# LTF1.net
KiCad netlist of a schematic drawn in EAGLE
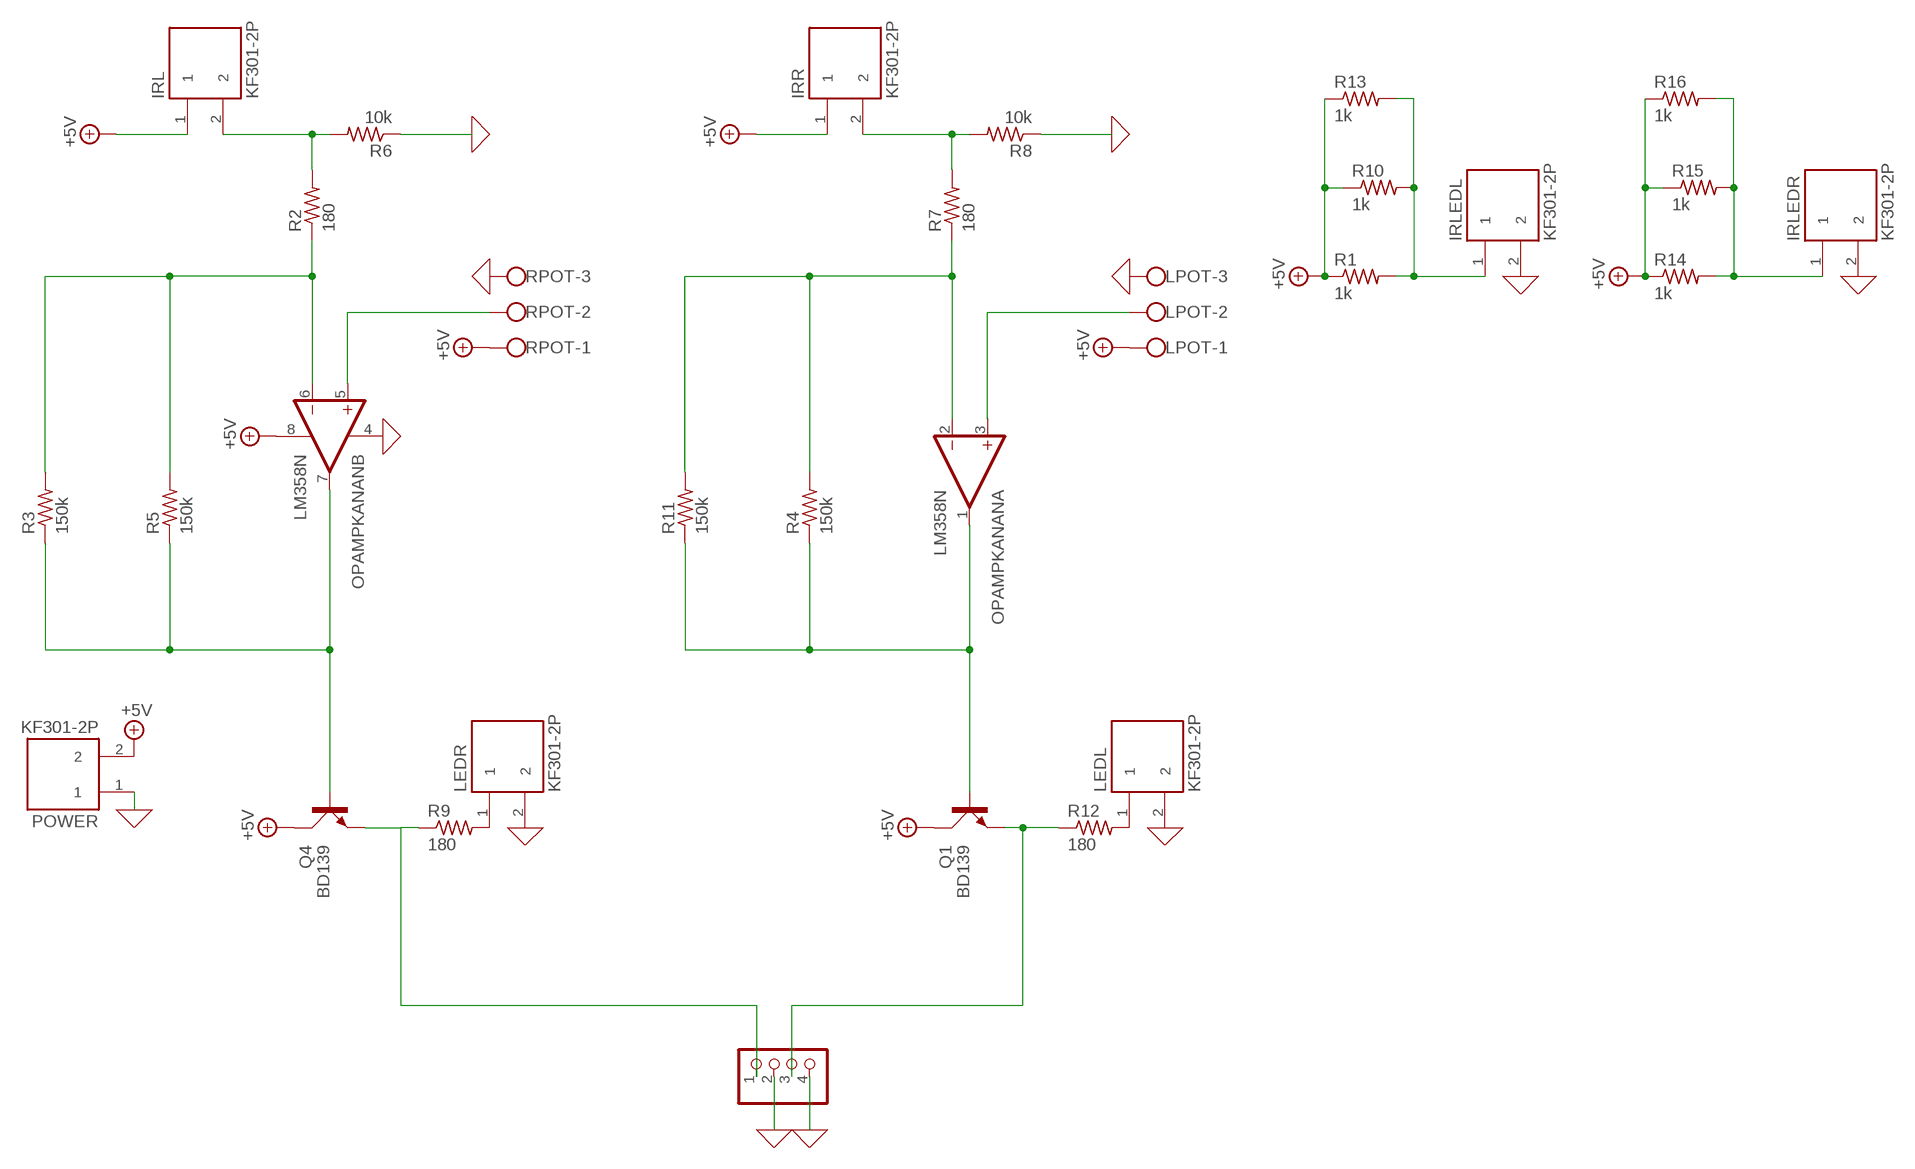
[diagram p0: schematic, sheet 1]

(export (version "E")
  (design (tool "Eeschema 10.0.6"))
  (components
    (comp (ref "IRL")
      (value "KF301-2P")
      (footprint "eagle-import:HANDSON_KF301-2P")
      (fields (field (name "MF") "Handson Technology"))
      (libsource (lib "eagle-import") (part "KF301-2P"))
    )
    (comp (ref "IRLEDL")
      (value "KF301-2P")
      (footprint "eagle-import:HANDSON_KF301-2P")
      (fields (field (name "MF") "Handson Technology"))
      (libsource (lib "eagle-import") (part "KF301-2P"))
    )
    (comp (ref "IRLEDR")
      (value "KF301-2P")
      (footprint "eagle-import:HANDSON_KF301-2P")
      (fields (field (name "MF") "Handson Technology"))
      (libsource (lib "eagle-import") (part "KF301-2P"))
    )
    (comp (ref "IRR")
      (value "KF301-2P")
      (footprint "eagle-import:HANDSON_KF301-2P")
      (fields (field (name "MF") "Handson Technology"))
      (libsource (lib "eagle-import") (part "KF301-2P"))
    )
    (comp (ref "LEDL")
      (value "KF301-2P")
      (footprint "eagle-import:HANDSON_KF301-2P")
      (fields (field (name "MF") "Handson Technology"))
      (libsource (lib "eagle-import") (part "KF301-2P"))
    )
    (comp (ref "LEDR")
      (value "KF301-2P")
      (footprint "eagle-import:HANDSON_KF301-2P")
      (fields (field (name "MF") "Handson Technology"))
      (libsource (lib "eagle-import") (part "KF301-2P"))
    )
    (comp (ref "LPOT")
      (value "W237-103")
      (footprint "eagle-import:W237-103")
      (fields (field (name "MPN") "237-103"))
      (libsource (lib "eagle-import") (part "W237-103"))
    )
    (comp (ref "MOTORDRIVER")
      (value "PINHD-1X4")
      (footprint "eagle-import:1X04")
      (libsource (lib "eagle-import") (part "PINHD-1X4"))
    )
    (comp (ref "OPAMPKANAN")
      (value "LM358N")
      (footprint "eagle-import:DIL08")
      (libsource (lib "eagle-import") (part "LM358N"))
    )
    (comp (ref "POWER")
      (value "KF301-2P")
      (footprint "eagle-import:HANDSON_KF301-2P")
      (fields (field (name "MF") "Handson Technology"))
      (libsource (lib "eagle-import") (part "KF301-2P"))
    )
    (comp (ref "Q1")
      (value "BD139")
      (footprint "eagle-import:TO126AV")
      (libsource (lib "eagle-import") (part "BD139"))
    )
    (comp (ref "Q4")
      (value "BD139")
      (footprint "eagle-import:TO126AV")
      (libsource (lib "eagle-import") (part "BD139"))
    )
    (comp (ref "R1")
      (value "1k")
      (footprint "eagle-import:0204_7")
      (libsource (lib "eagle-import") (part "R-US_0204/7"))
    )
    (comp (ref "R2")
      (value "180")
      (footprint "eagle-import:0204_7")
      (libsource (lib "eagle-import") (part "R-US_0204/7"))
    )
    (comp (ref "R3")
      (value "150k")
      (footprint "eagle-import:0204_7")
      (libsource (lib "eagle-import") (part "R-US_0204/7"))
    )
    (comp (ref "R4")
      (value "150k")
      (footprint "eagle-import:0204_7")
      (libsource (lib "eagle-import") (part "R-US_0204/7"))
    )
    (comp (ref "R5")
      (value "150k")
      (footprint "eagle-import:0204_7")
      (libsource (lib "eagle-import") (part "R-US_0204/7"))
    )
    (comp (ref "R6")
      (value "10k")
      (footprint "eagle-import:0204_7")
      (libsource (lib "eagle-import") (part "R-US_0204/7"))
    )
    (comp (ref "R7")
      (value "180")
      (footprint "eagle-import:0204_7")
      (libsource (lib "eagle-import") (part "R-US_0204/7"))
    )
    (comp (ref "R8")
      (value "10k")
      (footprint "eagle-import:0204_7")
      (libsource (lib "eagle-import") (part "R-US_0204/7"))
    )
    (comp (ref "R9")
      (value "180")
      (footprint "eagle-import:0204_7")
      (libsource (lib "eagle-import") (part "R-US_0204/7"))
    )
    (comp (ref "R10")
      (value "1k")
      (footprint "eagle-import:0204_7")
      (libsource (lib "eagle-import") (part "R-US_0204/7"))
    )
    (comp (ref "R11")
      (value "150k")
      (footprint "eagle-import:0204_7")
      (libsource (lib "eagle-import") (part "R-US_0204/7"))
    )
    (comp (ref "R12")
      (value "180")
      (footprint "eagle-import:0204_7")
      (libsource (lib "eagle-import") (part "R-US_0204/7"))
    )
    (comp (ref "R13")
      (value "1k")
      (footprint "eagle-import:0204_7")
      (libsource (lib "eagle-import") (part "R-US_0204/7"))
    )
    (comp (ref "R14")
      (value "1k")
      (footprint "eagle-import:0204_7")
      (libsource (lib "eagle-import") (part "R-US_0204/7"))
    )
    (comp (ref "R15")
      (value "1k")
      (footprint "eagle-import:0204_7")
      (libsource (lib "eagle-import") (part "R-US_0204/7"))
    )
    (comp (ref "R16")
      (value "1k")
      (footprint "eagle-import:0204_7")
      (libsource (lib "eagle-import") (part "R-US_0204/7"))
    )
    (comp (ref "RPOT")
      (value "W237-103")
      (footprint "eagle-import:W237-103")
      (fields (field (name "MPN") "237-103"))
      (libsource (lib "eagle-import") (part "W237-103"))
    )
  )
  (nets
    (net (code "1") (name "+5V") (class "Default")
      (node (ref "IRL") (pin "1") (pinfunction "1_1") (pintype "passive"))
      (node (ref "IRR") (pin "1") (pinfunction "1_1") (pintype "passive"))
      (node (ref "LPOT") (pin "1") (pinfunction "KL_1") (pintype "passive"))
      (node (ref "OPAMPKANAN") (pin "8") (pinfunction "V+_8") (pintype "power_in"))
      (node (ref "POWER") (pin "2") (pinfunction "2_2") (pintype "passive"))
      (node (ref "Q1") (pin "C") (pinfunction "C_C") (pintype "passive"))
      (node (ref "Q4") (pin "C") (pinfunction "C_C") (pintype "passive"))
      (node (ref "R1") (pin "1") (pinfunction "1_1") (pintype "passive"))
      (node (ref "R10") (pin "1") (pinfunction "1_1") (pintype "passive"))
      (node (ref "R13") (pin "1") (pinfunction "1_1") (pintype "passive"))
      (node (ref "R14") (pin "1") (pinfunction "1_1") (pintype "passive"))
      (node (ref "R15") (pin "1") (pinfunction "1_1") (pintype "passive"))
      (node (ref "R16") (pin "1") (pinfunction "1_1") (pintype "passive"))
      (node (ref "RPOT") (pin "1") (pinfunction "KL_1") (pintype "passive"))
    )
    (net (code "2") (name "GND") (class "Default")
      (node (ref "IRLEDL") (pin "2") (pinfunction "2_2") (pintype "passive"))
      (node (ref "IRLEDR") (pin "2") (pinfunction "2_2") (pintype "passive"))
      (node (ref "LEDL") (pin "2") (pinfunction "2_2") (pintype "passive"))
      (node (ref "LEDR") (pin "2") (pinfunction "2_2") (pintype "passive"))
      (node (ref "LPOT") (pin "3") (pinfunction "KL_3") (pintype "passive"))
      (node (ref "MOTORDRIVER") (pin "2") (pinfunction "2_2") (pintype "passive"))
      (node (ref "MOTORDRIVER") (pin "4") (pinfunction "4_4") (pintype "passive"))
      (node (ref "OPAMPKANAN") (pin "4") (pinfunction "V-_4") (pintype "power_in"))
      (node (ref "POWER") (pin "1") (pinfunction "1_1") (pintype "passive"))
      (node (ref "R6") (pin "1") (pinfunction "1_1") (pintype "passive"))
      (node (ref "R8") (pin "1") (pinfunction "1_1") (pintype "passive"))
      (node (ref "RPOT") (pin "3") (pinfunction "KL_3") (pintype "passive"))
    )
    (net (code "3") (name "Net-(IRL-Pad2)") (class "Default")
      (node (ref "IRL") (pin "2") (pinfunction "2_2") (pintype "passive"))
      (node (ref "R2") (pin "2") (pinfunction "2_2") (pintype "passive"))
      (node (ref "R6") (pin "2") (pinfunction "2_2") (pintype "passive"))
    )
    (net (code "4") (name "Net-(IRLEDL-Pad1)") (class "Default")
      (node (ref "IRLEDL") (pin "1") (pinfunction "1_1") (pintype "passive"))
      (node (ref "R1") (pin "2") (pinfunction "2_2") (pintype "passive"))
      (node (ref "R10") (pin "2") (pinfunction "2_2") (pintype "passive"))
      (node (ref "R13") (pin "2") (pinfunction "2_2") (pintype "passive"))
    )
    (net (code "5") (name "Net-(IRLEDR-Pad1)") (class "Default")
      (node (ref "IRLEDR") (pin "1") (pinfunction "1_1") (pintype "passive"))
      (node (ref "R14") (pin "2") (pinfunction "2_2") (pintype "passive"))
      (node (ref "R15") (pin "2") (pinfunction "2_2") (pintype "passive"))
      (node (ref "R16") (pin "2") (pinfunction "2_2") (pintype "passive"))
    )
    (net (code "6") (name "Net-(IRR-Pad2)") (class "Default")
      (node (ref "IRR") (pin "2") (pinfunction "2_2") (pintype "passive"))
      (node (ref "R7") (pin "2") (pinfunction "2_2") (pintype "passive"))
      (node (ref "R8") (pin "2") (pinfunction "2_2") (pintype "passive"))
    )
    (net (code "7") (name "Net-(LEDL-Pad1)") (class "Default")
      (node (ref "LEDL") (pin "1") (pinfunction "1_1") (pintype "passive"))
      (node (ref "R12") (pin "2") (pinfunction "2_2") (pintype "passive"))
    )
    (net (code "8") (name "Net-(LEDR-Pad1)") (class "Default")
      (node (ref "LEDR") (pin "1") (pinfunction "1_1") (pintype "passive"))
      (node (ref "R9") (pin "2") (pinfunction "2_2") (pintype "passive"))
    )
    (net (code "9") (name "Net-(LPOTB-KL)") (class "Default")
      (node (ref "LPOT") (pin "2") (pinfunction "KL_2") (pintype "passive"))
      (node (ref "OPAMPKANAN") (pin "3") (pinfunction "+IN_3") (pintype "input"))
    )
    (net (code "10") (name "Net-(MOTORDRIVER-Pad1)") (class "Default")
      (node (ref "MOTORDRIVER") (pin "1") (pinfunction "1_1") (pintype "passive"))
      (node (ref "Q4") (pin "E") (pinfunction "E_E") (pintype "passive"))
      (node (ref "R9") (pin "1") (pinfunction "1_1") (pintype "passive"))
    )
    (net (code "11") (name "Net-(MOTORDRIVER-Pad3)") (class "Default")
      (node (ref "MOTORDRIVER") (pin "3") (pinfunction "3_3") (pintype "passive"))
      (node (ref "Q1") (pin "E") (pinfunction "E_E") (pintype "passive"))
      (node (ref "R12") (pin "1") (pinfunction "1_1") (pintype "passive"))
    )
    (net (code "12") (name "Net-(OPAMPKANANA--IN)") (class "Default")
      (node (ref "OPAMPKANAN") (pin "2") (pinfunction "-IN_2") (pintype "input"))
      (node (ref "R11") (pin "2") (pinfunction "2_2") (pintype "passive"))
      (node (ref "R4") (pin "2") (pinfunction "2_2") (pintype "passive"))
      (node (ref "R7") (pin "1") (pinfunction "1_1") (pintype "passive"))
    )
    (net (code "13") (name "Net-(OPAMPKANANA-OUT)") (class "Default")
      (node (ref "OPAMPKANAN") (pin "1") (pinfunction "OUT_1") (pintype "output"))
      (node (ref "Q1") (pin "B") (pinfunction "B_B") (pintype "passive"))
      (node (ref "R11") (pin "1") (pinfunction "1_1") (pintype "passive"))
      (node (ref "R4") (pin "1") (pinfunction "1_1") (pintype "passive"))
    )
    (net (code "14") (name "Net-(OPAMPKANANB-+IN)") (class "Default")
      (node (ref "OPAMPKANAN") (pin "5") (pinfunction "+IN_5") (pintype "input"))
      (node (ref "RPOT") (pin "2") (pinfunction "KL_2") (pintype "passive"))
    )
    (net (code "15") (name "Net-(OPAMPKANANB--IN)") (class "Default")
      (node (ref "OPAMPKANAN") (pin "6") (pinfunction "-IN_6") (pintype "input"))
      (node (ref "R2") (pin "1") (pinfunction "1_1") (pintype "passive"))
      (node (ref "R3") (pin "2") (pinfunction "2_2") (pintype "passive"))
      (node (ref "R5") (pin "2") (pinfunction "2_2") (pintype "passive"))
    )
    (net (code "16") (name "Net-(OPAMPKANANB-OUT)") (class "Default")
      (node (ref "OPAMPKANAN") (pin "7") (pinfunction "OUT_7") (pintype "output"))
      (node (ref "Q4") (pin "B") (pinfunction "B_B") (pintype "passive"))
      (node (ref "R3") (pin "1") (pinfunction "1_1") (pintype "passive"))
      (node (ref "R5") (pin "1") (pinfunction "1_1") (pintype "passive"))
    )
  )
)
